# MiniRouter.net
KiCad netlist of a schematic drawn in EAGLE
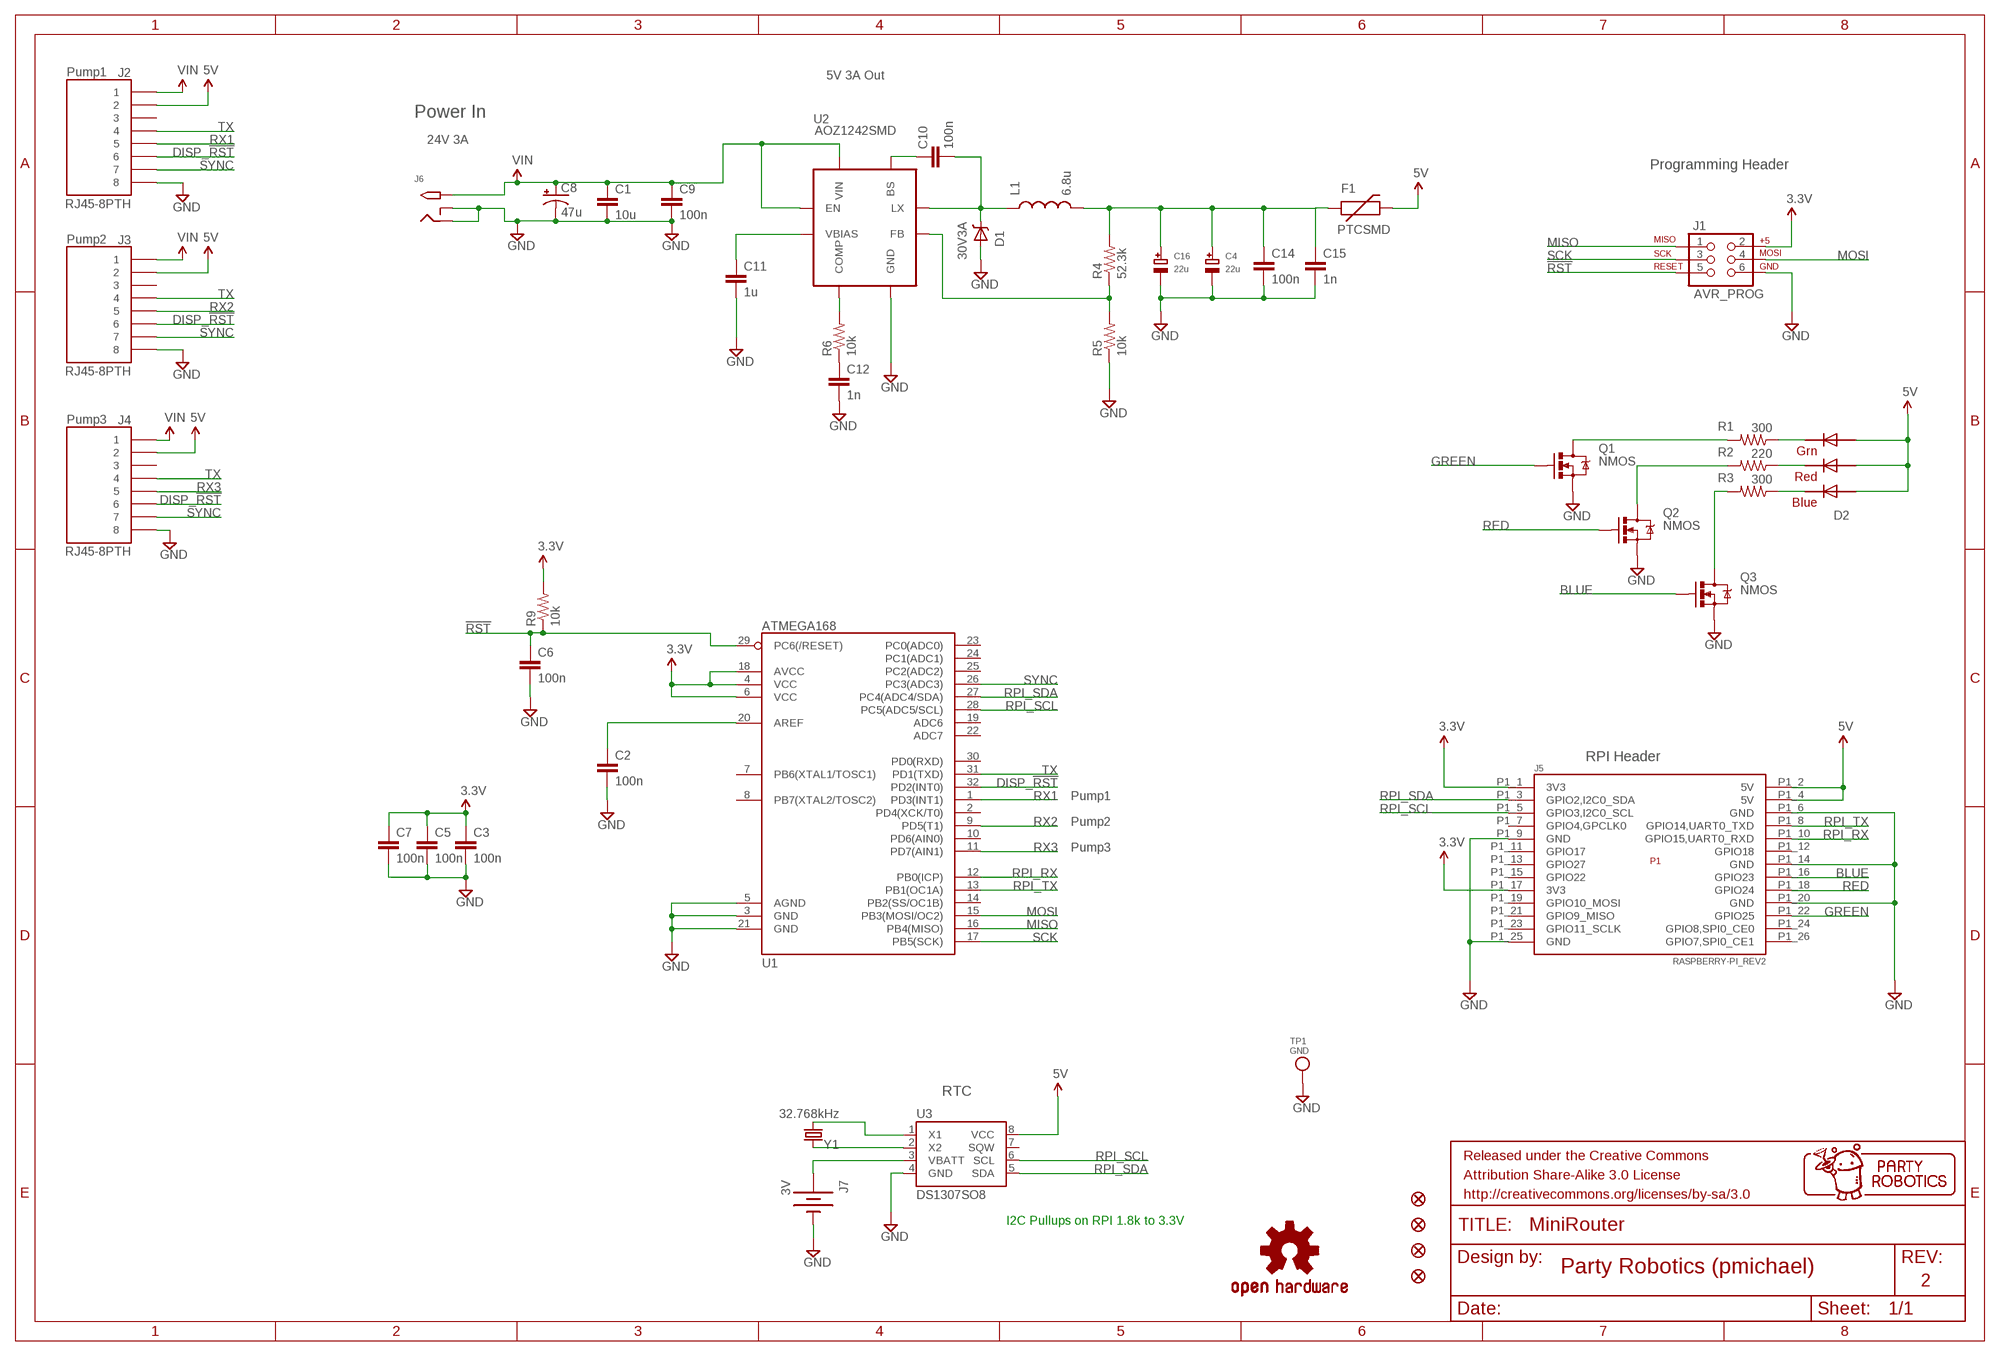
[diagram p0: schematic, sheet 1]

(export (version "E")
  (design (tool "Eeschema 10.0.6"))
  (components
    (comp (ref "C1")
      (value "10u")
      (footprint "eagle-import:1206")
      (libsource (lib "eagle-import") (part "SparkFun-Capacitors_CAP1206"))
    )
    (comp (ref "C2")
      (value "100n")
      (footprint "eagle-import:0603-CAP")
      (libsource (lib "eagle-import") (part "CAP0603-CAP"))
    )
    (comp (ref "C3")
      (value "100n")
      (footprint "eagle-import:0603-CAP")
      (libsource (lib "eagle-import") (part "CAP0603-CAP"))
    )
    (comp (ref "C4")
      (value "22u")
      (footprint "eagle-import:EIA6032-28_C-R")
      (libsource (lib "eagle-import") (part "CAP_TANTALUMC/6032_REFLOW"))
    )
    (comp (ref "C5")
      (value "100n")
      (footprint "eagle-import:0603-CAP")
      (libsource (lib "eagle-import") (part "CAP0603-CAP"))
    )
    (comp (ref "C6")
      (value "100n")
      (footprint "eagle-import:0603-CAP")
      (libsource (lib "eagle-import") (part "CAP0603-CAP"))
    )
    (comp (ref "C7")
      (value "100n")
      (footprint "eagle-import:0603-CAP")
      (libsource (lib "eagle-import") (part "CAP0603-CAP"))
    )
    (comp (ref "C8")
      (value "47u")
      (footprint "eagle-import:PANASONIC_D")
      (libsource (lib "eagle-import") (part "CAP_POLD"))
    )
    (comp (ref "C9")
      (value "100n")
      (footprint "eagle-import:0603-CAP")
      (libsource (lib "eagle-import") (part "CAP0603-CAP"))
    )
    (comp (ref "C10")
      (value "100n")
      (footprint "eagle-import:0603-CAP")
      (libsource (lib "eagle-import") (part "CAP0603-CAP"))
    )
    (comp (ref "C11")
      (value "1u")
      (footprint "eagle-import:0603-CAP")
      (libsource (lib "eagle-import") (part "CAP0603-CAP"))
    )
    (comp (ref "C12")
      (value "1n")
      (footprint "eagle-import:0603-CAP")
      (libsource (lib "eagle-import") (part "CAP0603-CAP"))
    )
    (comp (ref "C14")
      (value "100n")
      (footprint "eagle-import:0603-CAP")
      (libsource (lib "eagle-import") (part "CAP0603-CAP"))
    )
    (comp (ref "C15")
      (value "1n")
      (footprint "eagle-import:0603-CAP")
      (libsource (lib "eagle-import") (part "CAP0603-CAP"))
    )
    (comp (ref "C16")
      (value "22u")
      (footprint "eagle-import:EIA6032-28_C-R")
      (libsource (lib "eagle-import") (part "CAP_TANTALUMC/6032_REFLOW"))
    )
    (comp (ref "D1")
      (value "30V3A")
      (footprint "eagle-import:SMA-DIODE")
      (libsource (lib "eagle-import") (part "B330A"))
    )
    (comp (ref "D2")
      (value "RGBLED5050")
      (footprint "eagle-import:RGBLED5050")
      (libsource (lib "eagle-import") (part "RGBLED5050"))
    )
    (comp (ref "F1")
      (value "PTCSMD")
      (footprint "eagle-import:PTC-1206")
      (libsource (lib "eagle-import") (part "PTCSMD"))
    )
    (comp (ref "FRAME3")
      (value "FRAME-LETTER")
      (footprint "eagle-import:CREATIVE_COMMONS")
      (libsource (lib "eagle-import") (part "FRAME-LETTER"))
    )
    (comp (ref "J1")
      (value "AVR_PROG")
      (footprint "eagle-import:2X3_LOCK")
      (libsource (lib "eagle-import") (part "AVR_SPI_PRG_62X3_LOCK"))
    )
    (comp (ref "J2")
      (value "RJ45-8PTH")
      (footprint "eagle-import:RJ45-8")
      (libsource (lib "eagle-import") (part "RJ45-8PTH"))
    )
    (comp (ref "J3")
      (value "RJ45-8PTH")
      (footprint "eagle-import:RJ45-8")
      (libsource (lib "eagle-import") (part "RJ45-8PTH"))
    )
    (comp (ref "J4")
      (value "RJ45-8PTH")
      (footprint "eagle-import:RJ45-8")
      (libsource (lib "eagle-import") (part "RJ45-8PTH"))
    )
    (comp (ref "J5")
      (value "RASPBERRY-PI_REV2")
      (footprint "eagle-import:RASPBERRY-PI_REV2")
      (libsource (lib "eagle-import") (part "RASPBERRY-PI_REV2"))
    )
    (comp (ref "J6")
      (value "2.1MMJACKTHM")
      (footprint "eagle-import:PJ-102A")
      (libsource (lib "eagle-import") (part "2.1MMJACKTHM"))
    )
    (comp (ref "J7")
      (value "3V")
      (footprint "eagle-import:BATTCON_12MM_PTH")
      (libsource (lib "eagle-import") (part "BATTERY12PTH"))
    )
    (comp (ref "JP1")
      (value "FIDUCIAL1.5X3")
      (footprint "eagle-import:FIDUCIAL-1.5X3")
      (libsource (lib "eagle-import") (part "FIDUCIAL1.5X3"))
    )
    (comp (ref "JP2")
      (value "FIDUCIAL1.5X3")
      (footprint "eagle-import:FIDUCIAL-1.5X3")
      (libsource (lib "eagle-import") (part "FIDUCIAL1.5X3"))
    )
    (comp (ref "JP3")
      (value "FIDUCIAL1.5X3")
      (footprint "eagle-import:FIDUCIAL-1.5X3")
      (libsource (lib "eagle-import") (part "FIDUCIAL1.5X3"))
    )
    (comp (ref "JP4")
      (value "FIDUCIAL1.5X3")
      (footprint "eagle-import:FIDUCIAL-1.5X3")
      (libsource (lib "eagle-import") (part "FIDUCIAL1.5X3"))
    )
    (comp (ref "L1")
      (value "6.8u")
      (footprint "eagle-import:IND_8X8X4")
      (libsource (lib "eagle-import") (part "INDUCTORCR54"))
    )
    (comp (ref "Q1")
      (value "NMOS")
      (footprint "eagle-import:SOT23-3")
      (libsource (lib "eagle-import") (part "MOSFET-NCHANNELSMD"))
    )
    (comp (ref "Q2")
      (value "NMOS")
      (footprint "eagle-import:SOT23-3")
      (libsource (lib "eagle-import") (part "MOSFET-NCHANNELSMD"))
    )
    (comp (ref "Q3")
      (value "NMOS")
      (footprint "eagle-import:SOT23-3")
      (libsource (lib "eagle-import") (part "MOSFET-NCHANNELSMD"))
    )
    (comp (ref "R1")
      (value "300")
      (footprint "eagle-import:0603-RES")
      (libsource (lib "eagle-import") (part "RESISTOR0603-RES"))
    )
    (comp (ref "R2")
      (value "220")
      (footprint "eagle-import:0603-RES")
      (libsource (lib "eagle-import") (part "RESISTOR0603-RES"))
    )
    (comp (ref "R3")
      (value "300")
      (footprint "eagle-import:0603-RES")
      (libsource (lib "eagle-import") (part "RESISTOR0603-RES"))
    )
    (comp (ref "R4")
      (value "52.3k")
      (footprint "eagle-import:0603-RES")
      (libsource (lib "eagle-import") (part "RESISTOR0603-RES"))
    )
    (comp (ref "R5")
      (value "10k")
      (footprint "eagle-import:0603-RES")
      (libsource (lib "eagle-import") (part "RESISTOR0603-RES"))
    )
    (comp (ref "R6")
      (value "10k")
      (footprint "eagle-import:0603-RES")
      (libsource (lib "eagle-import") (part "RESISTOR0603-RES"))
    )
    (comp (ref "R9")
      (value "10k")
      (footprint "eagle-import:0603-RES")
      (libsource (lib "eagle-import") (part "RESISTOR0603-RES"))
    )
    (comp (ref "TP1")
      (value "GND")
      (footprint "eagle-import:TESTPOINT_SMT")
      (libsource (lib "eagle-import") (part "TESTPOINT"))
    )
    (comp (ref "U$46")
      (value "OSHW-LOGOM")
      (footprint "eagle-import:OSHW-LOGO-M")
      (libsource (lib "eagle-import") (part "OSHW-LOGOM"))
    )
    (comp (ref "U1")
      (value "ATMEGA168")
      (footprint "eagle-import:TQFP32-08")
      (libsource (lib "eagle-import") (part "ATMEGA168"))
    )
    (comp (ref "U2")
      (value "AOZ1242SMD")
      (footprint "eagle-import:SO08")
      (libsource (lib "eagle-import") (part "AOZ1242SMD"))
    )
    (comp (ref "U3")
      (value "DS1307SO8")
      (footprint "eagle-import:SO08")
      (libsource (lib "eagle-import") (part "DS1307SO8"))
    )
    (comp (ref "Y1")
      (value "32.768kHz")
      (footprint "eagle-import:TC26HEZ")
      (libsource (lib "eagle-import") (part "CRYSTALTC26H_EZ"))
    )
  )
  (nets
    (net (code "1") (name "/BLUE") (class "Default")
      (node (ref "J5") (pin "P1_16") (pinfunction "GPIO23_P1_16") (pintype "bidirectional"))
      (node (ref "Q3") (pin "1") (pinfunction "G_1") (pintype "passive"))
    )
    (net (code "2") (name "/DISP_~{RST}") (class "Default")
      (node (ref "J2") (pin "6") (pinfunction "6_6") (pintype "bidirectional"))
      (node (ref "J3") (pin "6") (pinfunction "6_6") (pintype "bidirectional"))
      (node (ref "J4") (pin "6") (pinfunction "6_6") (pintype "bidirectional"))
      (node (ref "U1") (pin "32") (pinfunction "PD2(INT0)_32") (pintype "bidirectional"))
    )
    (net (code "3") (name "/GREEN") (class "Default")
      (node (ref "J5") (pin "P1_22") (pinfunction "GPIO25_P1_22") (pintype "bidirectional"))
      (node (ref "Q1") (pin "1") (pinfunction "G_1") (pintype "passive"))
    )
    (net (code "4") (name "/MISO") (class "Default")
      (node (ref "J1") (pin "1") (pinfunction "1_1") (pintype "passive"))
      (node (ref "U1") (pin "16") (pinfunction "PB4(MISO)_16") (pintype "bidirectional"))
    )
    (net (code "5") (name "/MOSI") (class "Default")
      (node (ref "J1") (pin "4") (pinfunction "4_4") (pintype "passive"))
      (node (ref "U1") (pin "15") (pinfunction "PB3(MOSI/OC2)_15") (pintype "bidirectional"))
    )
    (net (code "6") (name "/RED") (class "Default")
      (node (ref "J5") (pin "P1_18") (pinfunction "GPIO24_P1_18") (pintype "bidirectional"))
      (node (ref "Q2") (pin "1") (pinfunction "G_1") (pintype "passive"))
    )
    (net (code "7") (name "/RPI_RX") (class "Default")
      (node (ref "J5") (pin "P1_10") (pinfunction "GPIO15,UART0_RXD_P1_10") (pintype "bidirectional"))
      (node (ref "U1") (pin "12") (pinfunction "PB0(ICP)_12") (pintype "bidirectional"))
    )
    (net (code "8") (name "/RPI_SCL") (class "Default")
      (node (ref "J5") (pin "P1_5") (pinfunction "GPIO3,I2C0_SCL_P1_5") (pintype "bidirectional"))
      (node (ref "U1") (pin "28") (pinfunction "PC5(ADC5/SCL)_28") (pintype "bidirectional"))
      (node (ref "U3") (pin "6") (pinfunction "SCL_6") (pintype "bidirectional"))
    )
    (net (code "9") (name "/RPI_SDA") (class "Default")
      (node (ref "J5") (pin "P1_3") (pinfunction "GPIO2,I2C0_SDA_P1_3") (pintype "bidirectional"))
      (node (ref "U1") (pin "27") (pinfunction "PC4(ADC4/SDA)_27") (pintype "bidirectional"))
      (node (ref "U3") (pin "5") (pinfunction "SDA_5") (pintype "bidirectional"))
    )
    (net (code "10") (name "/RPI_TX") (class "Default")
      (node (ref "J5") (pin "P1_8") (pinfunction "GPIO14,UART0_TXD_P1_8") (pintype "bidirectional"))
      (node (ref "U1") (pin "13") (pinfunction "PB1(OC1A)_13") (pintype "bidirectional"))
    )
    (net (code "11") (name "/RX1") (class "Default")
      (node (ref "J2") (pin "5") (pinfunction "5_5") (pintype "bidirectional"))
      (node (ref "U1") (pin "1") (pinfunction "PD3(INT1)_1") (pintype "bidirectional"))
    )
    (net (code "12") (name "/RX2") (class "Default")
      (node (ref "J3") (pin "5") (pinfunction "5_5") (pintype "bidirectional"))
      (node (ref "U1") (pin "9") (pinfunction "PD5(T1)_9") (pintype "bidirectional"))
    )
    (net (code "13") (name "/RX3") (class "Default")
      (node (ref "J4") (pin "5") (pinfunction "5_5") (pintype "bidirectional"))
      (node (ref "U1") (pin "11") (pinfunction "PD7(AIN1)_11") (pintype "bidirectional"))
    )
    (net (code "14") (name "/SCK") (class "Default")
      (node (ref "J1") (pin "3") (pinfunction "3_3") (pintype "passive"))
      (node (ref "U1") (pin "17") (pinfunction "PB5(SCK)_17") (pintype "bidirectional"))
    )
    (net (code "15") (name "/SYNC") (class "Default")
      (node (ref "J2") (pin "7") (pinfunction "7_7") (pintype "bidirectional"))
      (node (ref "J3") (pin "7") (pinfunction "7_7") (pintype "bidirectional"))
      (node (ref "J4") (pin "7") (pinfunction "7_7") (pintype "bidirectional"))
      (node (ref "U1") (pin "26") (pinfunction "PC3(ADC3)_26") (pintype "bidirectional"))
    )
    (net (code "16") (name "/TX") (class "Default")
      (node (ref "J2") (pin "4") (pinfunction "4_4") (pintype "bidirectional"))
      (node (ref "J3") (pin "4") (pinfunction "4_4") (pintype "bidirectional"))
      (node (ref "J4") (pin "4") (pinfunction "4_4") (pintype "bidirectional"))
      (node (ref "U1") (pin "31") (pinfunction "PD1(TXD)_31") (pintype "bidirectional"))
    )
    (net (code "17") (name "/~{RST}") (class "Default")
      (node (ref "C6") (pin "1") (pinfunction "1_1") (pintype "passive"))
      (node (ref "J1") (pin "5") (pinfunction "5_5") (pintype "passive"))
      (node (ref "R9") (pin "1") (pinfunction "1_1") (pintype "passive"))
      (node (ref "U1") (pin "29") (pinfunction "PC6(/RESET)_29") (pintype "bidirectional"))
    )
    (net (code "18") (name "3.3V") (class "Default")
      (node (ref "C3") (pin "1") (pinfunction "1_1") (pintype "passive"))
      (node (ref "C5") (pin "1") (pinfunction "1_1") (pintype "passive"))
      (node (ref "C7") (pin "1") (pinfunction "1_1") (pintype "passive"))
      (node (ref "J1") (pin "2") (pinfunction "2_2") (pintype "passive"))
      (node (ref "J5") (pin "P1_1") (pinfunction "3V3_P1_1") (pintype "bidirectional"))
      (node (ref "J5") (pin "P1_17") (pinfunction "3V3_P1_17") (pintype "bidirectional"))
      (node (ref "R9") (pin "2") (pinfunction "2_2") (pintype "passive"))
      (node (ref "U1") (pin "18") (pinfunction "AVCC_18") (pintype "bidirectional"))
      (node (ref "U1") (pin "4") (pinfunction "VCC_4") (pintype "bidirectional"))
      (node (ref "U1") (pin "6") (pinfunction "VCC_6") (pintype "bidirectional"))
    )
    (net (code "19") (name "5V") (class "Default")
      (node (ref "D2") (pin "1") (pinfunction "BLUE_A_1") (pintype "bidirectional"))
      (node (ref "D2") (pin "2") (pinfunction "RED_A_2") (pintype "bidirectional"))
      (node (ref "D2") (pin "3") (pinfunction "GREEN_A_3") (pintype "bidirectional"))
      (node (ref "F1") (pin "2") (pinfunction "2_2") (pintype "bidirectional"))
      (node (ref "J2") (pin "2") (pinfunction "2_2") (pintype "bidirectional"))
      (node (ref "J3") (pin "2") (pinfunction "2_2") (pintype "bidirectional"))
      (node (ref "J4") (pin "2") (pinfunction "2_2") (pintype "bidirectional"))
      (node (ref "J5") (pin "P1_2") (pinfunction "5V_P1_2") (pintype "bidirectional"))
      (node (ref "J5") (pin "P1_4") (pinfunction "5V_P1_4") (pintype "bidirectional"))
      (node (ref "U3") (pin "8") (pinfunction "VCC_8") (pintype "bidirectional"))
    )
    (net (code "20") (name "GND") (class "Default")
      (node (ref "C1") (pin "2") (pinfunction "2_2") (pintype "passive"))
      (node (ref "C11") (pin "2") (pinfunction "2_2") (pintype "passive"))
      (node (ref "C12") (pin "2") (pinfunction "2_2") (pintype "passive"))
      (node (ref "C14") (pin "2") (pinfunction "2_2") (pintype "passive"))
      (node (ref "C15") (pin "2") (pinfunction "2_2") (pintype "passive"))
      (node (ref "C16") (pin "-") (pinfunction "-_-") (pintype "passive"))
      (node (ref "C2") (pin "2") (pinfunction "2_2") (pintype "passive"))
      (node (ref "C3") (pin "2") (pinfunction "2_2") (pintype "passive"))
      (node (ref "C4") (pin "-") (pinfunction "-_-") (pintype "passive"))
      (node (ref "C5") (pin "2") (pinfunction "2_2") (pintype "passive"))
      (node (ref "C6") (pin "2") (pinfunction "2_2") (pintype "passive"))
      (node (ref "C7") (pin "2") (pinfunction "2_2") (pintype "passive"))
      (node (ref "C8") (pin "-") (pinfunction "-_-") (pintype "passive"))
      (node (ref "C9") (pin "2") (pinfunction "2_2") (pintype "passive"))
      (node (ref "D1") (pin "A") (pinfunction "A_A") (pintype "passive"))
      (node (ref "J1") (pin "6") (pinfunction "6_6") (pintype "passive"))
      (node (ref "J2") (pin "8") (pinfunction "8_8") (pintype "bidirectional"))
      (node (ref "J3") (pin "8") (pinfunction "8_8") (pintype "bidirectional"))
      (node (ref "J4") (pin "8") (pinfunction "8_8") (pintype "bidirectional"))
      (node (ref "J5") (pin "P1_14") (pinfunction "GND_P1_14") (pintype "bidirectional"))
      (node (ref "J5") (pin "P1_20") (pinfunction "GND_P1_20") (pintype "bidirectional"))
      (node (ref "J5") (pin "P1_25") (pinfunction "GND_P1_25") (pintype "bidirectional"))
      (node (ref "J5") (pin "P1_6") (pinfunction "GND_P1_6") (pintype "bidirectional"))
      (node (ref "J5") (pin "P1_9") (pinfunction "GND_P1_9") (pintype "bidirectional"))
      (node (ref "J6") (pin "RING") (pinfunction "RING_RING") (pintype "bidirectional"))
      (node (ref "J6") (pin "RING_SW") (pinfunction "RING_SW_RING_SW") (pintype "bidirectional"))
      (node (ref "J7") (pin "GND") (pinfunction "-_GND") (pintype "power_in"))
      (node (ref "Q1") (pin "2") (pinfunction "S_2") (pintype "passive"))
      (node (ref "Q2") (pin "2") (pinfunction "S_2") (pintype "passive"))
      (node (ref "Q3") (pin "2") (pinfunction "S_2") (pintype "passive"))
      (node (ref "R5") (pin "1") (pinfunction "1_1") (pintype "passive"))
      (node (ref "TP1") (pin "P$1") (pinfunction "P$1_P$1") (pintype "bidirectional"))
      (node (ref "U1") (pin "21") (pinfunction "GND_21") (pintype "bidirectional"))
      (node (ref "U1") (pin "3") (pinfunction "GND_3") (pintype "bidirectional"))
      (node (ref "U1") (pin "5") (pinfunction "AGND_5") (pintype "bidirectional"))
      (node (ref "U2") (pin "3") (pinfunction "GND_3") (pintype "bidirectional"))
      (node (ref "U3") (pin "4") (pinfunction "GND_4") (pintype "bidirectional"))
    )
    (net (code "21") (name "Net-(C12-Pad1)") (class "Default")
      (node (ref "C12") (pin "1") (pinfunction "1_1") (pintype "passive"))
      (node (ref "R6") (pin "1") (pinfunction "1_1") (pintype "passive"))
    )
    (net (code "22") (name "Net-(D2-BLUE_C)") (class "Default")
      (node (ref "D2") (pin "6") (pinfunction "BLUE_C_6") (pintype "bidirectional"))
      (node (ref "R3") (pin "1") (pinfunction "1_1") (pintype "passive"))
    )
    (net (code "23") (name "Net-(D2-GREEN_C)") (class "Default")
      (node (ref "D2") (pin "4") (pinfunction "GREEN_C_4") (pintype "bidirectional"))
      (node (ref "R1") (pin "1") (pinfunction "1_1") (pintype "passive"))
    )
    (net (code "24") (name "Net-(D2-RED_C)") (class "Default")
      (node (ref "D2") (pin "5") (pinfunction "RED_C_5") (pintype "bidirectional"))
      (node (ref "R2") (pin "1") (pinfunction "1_1") (pintype "passive"))
    )
    (net (code "25") (name "Net-(J7-+)") (class "Default")
      (node (ref "J7") (pin "VCC@1") (pinfunction "+_VCC@1") (pintype "power_in"))
      (node (ref "U3") (pin "3") (pinfunction "VBATT_3") (pintype "bidirectional"))
    )
    (net (code "26") (name "Net-(L1-1)") (class "Default")
      (node (ref "C10") (pin "2") (pinfunction "2_2") (pintype "passive"))
      (node (ref "D1") (pin "C") (pinfunction "C_C") (pintype "passive"))
      (node (ref "L1") (pin "P$1") (pinfunction "1_P$1") (pintype "passive"))
      (node (ref "U2") (pin "1") (pinfunction "LX_1") (pintype "bidirectional"))
    )
    (net (code "27") (name "Net-(L1-2)") (class "Default")
      (node (ref "C14") (pin "1") (pinfunction "1_1") (pintype "passive"))
      (node (ref "C15") (pin "1") (pinfunction "1_1") (pintype "passive"))
      (node (ref "C16") (pin "+") (pinfunction "+_+") (pintype "passive"))
      (node (ref "C4") (pin "+") (pinfunction "+_+") (pintype "passive"))
      (node (ref "F1") (pin "1") (pinfunction "1_1") (pintype "bidirectional"))
      (node (ref "L1") (pin "P$2") (pinfunction "2_P$2") (pintype "passive"))
      (node (ref "R4") (pin "2") (pinfunction "2_2") (pintype "passive"))
    )
    (net (code "28") (name "Net-(Q1-D)") (class "Default")
      (node (ref "Q1") (pin "3") (pinfunction "D_3") (pintype "passive"))
      (node (ref "R1") (pin "2") (pinfunction "2_2") (pintype "passive"))
    )
    (net (code "29") (name "Net-(Q2-D)") (class "Default")
      (node (ref "Q2") (pin "3") (pinfunction "D_3") (pintype "passive"))
      (node (ref "R2") (pin "2") (pinfunction "2_2") (pintype "passive"))
    )
    (net (code "30") (name "Net-(Q3-D)") (class "Default")
      (node (ref "Q3") (pin "3") (pinfunction "D_3") (pintype "passive"))
      (node (ref "R3") (pin "2") (pinfunction "2_2") (pintype "passive"))
    )
    (net (code "31") (name "Net-(U1-AREF)") (class "Default")
      (node (ref "C2") (pin "1") (pinfunction "1_1") (pintype "passive"))
      (node (ref "U1") (pin "20") (pinfunction "AREF_20") (pintype "bidirectional"))
    )
    (net (code "32") (name "Net-(U2-BS)") (class "Default")
      (node (ref "C10") (pin "1") (pinfunction "1_1") (pintype "passive"))
      (node (ref "U2") (pin "2") (pinfunction "BS_2") (pintype "bidirectional"))
    )
    (net (code "33") (name "Net-(U2-COMP)") (class "Default")
      (node (ref "R6") (pin "2") (pinfunction "2_2") (pintype "passive"))
      (node (ref "U2") (pin "5") (pinfunction "COMP_5") (pintype "bidirectional"))
    )
    (net (code "34") (name "Net-(U2-FB)") (class "Default")
      (node (ref "R4") (pin "1") (pinfunction "1_1") (pintype "passive"))
      (node (ref "R5") (pin "2") (pinfunction "2_2") (pintype "passive"))
      (node (ref "U2") (pin "4") (pinfunction "FB_4") (pintype "bidirectional"))
    )
    (net (code "35") (name "Net-(U2-VBIAS)") (class "Default")
      (node (ref "C11") (pin "1") (pinfunction "1_1") (pintype "passive"))
      (node (ref "U2") (pin "8") (pinfunction "VBIAS_8") (pintype "bidirectional"))
    )
    (net (code "36") (name "Net-(U3-X1)") (class "Default")
      (node (ref "U3") (pin "1") (pinfunction "X1_1") (pintype "bidirectional"))
      (node (ref "Y1") (pin "2") (pinfunction "2_2") (pintype "passive"))
    )
    (net (code "37") (name "Net-(U3-X2)") (class "Default")
      (node (ref "U3") (pin "2") (pinfunction "X2_2") (pintype "bidirectional"))
      (node (ref "Y1") (pin "1") (pinfunction "1_1") (pintype "passive"))
    )
    (net (code "38") (name "VIN") (class "Default")
      (node (ref "C1") (pin "1") (pinfunction "1_1") (pintype "passive"))
      (node (ref "C8") (pin "+") (pinfunction "+_+") (pintype "passive"))
      (node (ref "C9") (pin "1") (pinfunction "1_1") (pintype "passive"))
      (node (ref "J2") (pin "1") (pinfunction "1_1") (pintype "bidirectional"))
      (node (ref "J3") (pin "1") (pinfunction "1_1") (pintype "bidirectional"))
      (node (ref "J4") (pin "1") (pinfunction "1_1") (pintype "bidirectional"))
      (node (ref "J6") (pin "TIP") (pinfunction "TIP_TIP") (pintype "bidirectional"))
      (node (ref "U2") (pin "6") (pinfunction "EN_6") (pintype "bidirectional"))
      (node (ref "U2") (pin "7") (pinfunction "VIN_7") (pintype "bidirectional"))
    )
    (net (code "39") (name "unconnected-(J2-Pad3)") (class "Default")
      (node (ref "J2") (pin "3") (pinfunction "3_3") (pintype "bidirectional"))
    )
    (net (code "40") (name "unconnected-(J3-Pad3)") (class "Default")
      (node (ref "J3") (pin "3") (pinfunction "3_3") (pintype "bidirectional"))
    )
    (net (code "41") (name "unconnected-(J4-Pad3)") (class "Default")
      (node (ref "J4") (pin "3") (pinfunction "3_3") (pintype "bidirectional"))
    )
    (net (code "42") (name "unconnected-(J5-GPIO4,GPCLK0-PadP1_7)") (class "Default")
      (node (ref "J5") (pin "P1_7") (pinfunction "GPIO4,GPCLK0_P1_7") (pintype "bidirectional"))
    )
    (net (code "43") (name "unconnected-(J5-GPIO7,SPI0_CE1-PadP1_26)") (class "Default")
      (node (ref "J5") (pin "P1_26") (pinfunction "GPIO7,SPI0_CE1_P1_26") (pintype "bidirectional"))
    )
    (net (code "44") (name "unconnected-(J5-GPIO8,SPI0_CE0-PadP1_24)") (class "Default")
      (node (ref "J5") (pin "P1_24") (pinfunction "GPIO8,SPI0_CE0_P1_24") (pintype "bidirectional"))
    )
    (net (code "45") (name "unconnected-(J5-GPIO9_MISO-PadP1_21)") (class "Default")
      (node (ref "J5") (pin "P1_21") (pinfunction "GPIO9_MISO_P1_21") (pintype "bidirectional"))
    )
    (net (code "46") (name "unconnected-(J5-GPIO10_MOSI-PadP1_19)") (class "Default")
      (node (ref "J5") (pin "P1_19") (pinfunction "GPIO10_MOSI_P1_19") (pintype "bidirectional"))
    )
    (net (code "47") (name "unconnected-(J5-GPIO11_SCLK-PadP1_23)") (class "Default")
      (node (ref "J5") (pin "P1_23") (pinfunction "GPIO11_SCLK_P1_23") (pintype "bidirectional"))
    )
    (net (code "48") (name "unconnected-(J5-GPIO17-PadP1_11)") (class "Default")
      (node (ref "J5") (pin "P1_11") (pinfunction "GPIO17_P1_11") (pintype "bidirectional"))
    )
    (net (code "49") (name "unconnected-(J5-GPIO18-PadP1_12)") (class "Default")
      (node (ref "J5") (pin "P1_12") (pinfunction "GPIO18_P1_12") (pintype "bidirectional"))
    )
    (net (code "50") (name "unconnected-(J5-GPIO22-PadP1_15)") (class "Default")
      (node (ref "J5") (pin "P1_15") (pinfunction "GPIO22_P1_15") (pintype "bidirectional"))
    )
    (net (code "51") (name "unconnected-(J5-GPIO27-PadP1_13)") (class "Default")
      (node (ref "J5") (pin "P1_13") (pinfunction "GPIO27_P1_13") (pintype "bidirectional"))
    )
    (net (code "52") (name "unconnected-(U1-ADC6-Pad19)") (class "Default")
      (node (ref "U1") (pin "19") (pinfunction "ADC6_19") (pintype "bidirectional"))
    )
    (net (code "53") (name "unconnected-(U1-ADC7-Pad22)") (class "Default")
      (node (ref "U1") (pin "22") (pinfunction "ADC7_22") (pintype "bidirectional"))
    )
    (net (code "54") (name "unconnected-(U1-PB2(SS{slash}OC1B)-Pad14)") (class "Default")
      (node (ref "U1") (pin "14") (pinfunction "PB2(SS/OC1B)_14") (pintype "bidirectional"))
    )
    (net (code "55") (name "unconnected-(U1-PB6(XTAL1{slash}TOSC1)-Pad7)") (class "Default")
      (node (ref "U1") (pin "7") (pinfunction "PB6(XTAL1/TOSC1)_7") (pintype "bidirectional"))
    )
    (net (code "56") (name "unconnected-(U1-PB7(XTAL2{slash}TOSC2)-Pad8)") (class "Default")
      (node (ref "U1") (pin "8") (pinfunction "PB7(XTAL2/TOSC2)_8") (pintype "bidirectional"))
    )
    (net (code "57") (name "unconnected-(U1-PC0(ADC0)-Pad23)") (class "Default")
      (node (ref "U1") (pin "23") (pinfunction "PC0(ADC0)_23") (pintype "bidirectional"))
    )
    (net (code "58") (name "unconnected-(U1-PC1(ADC1)-Pad24)") (class "Default")
      (node (ref "U1") (pin "24") (pinfunction "PC1(ADC1)_24") (pintype "bidirectional"))
    )
    (net (code "59") (name "unconnected-(U1-PC2(ADC2)-Pad25)") (class "Default")
      (node (ref "U1") (pin "25") (pinfunction "PC2(ADC2)_25") (pintype "bidirectional"))
    )
    (net (code "60") (name "unconnected-(U1-PD0(RXD)-Pad30)") (class "Default")
      (node (ref "U1") (pin "30") (pinfunction "PD0(RXD)_30") (pintype "bidirectional"))
    )
    (net (code "61") (name "unconnected-(U1-PD4(XCK{slash}T0)-Pad2)") (class "Default")
      (node (ref "U1") (pin "2") (pinfunction "PD4(XCK/T0)_2") (pintype "bidirectional"))
    )
    (net (code "62") (name "unconnected-(U1-PD6(AIN0)-Pad10)") (class "Default")
      (node (ref "U1") (pin "10") (pinfunction "PD6(AIN0)_10") (pintype "bidirectional"))
    )
    (net (code "63") (name "unconnected-(U3-SQW-Pad7)") (class "Default")
      (node (ref "U3") (pin "7") (pinfunction "SQW_7") (pintype "bidirectional"))
    )
  )
)
